# Add-OnV12.net
KiCad netlist of a schematic drawn in EAGLE
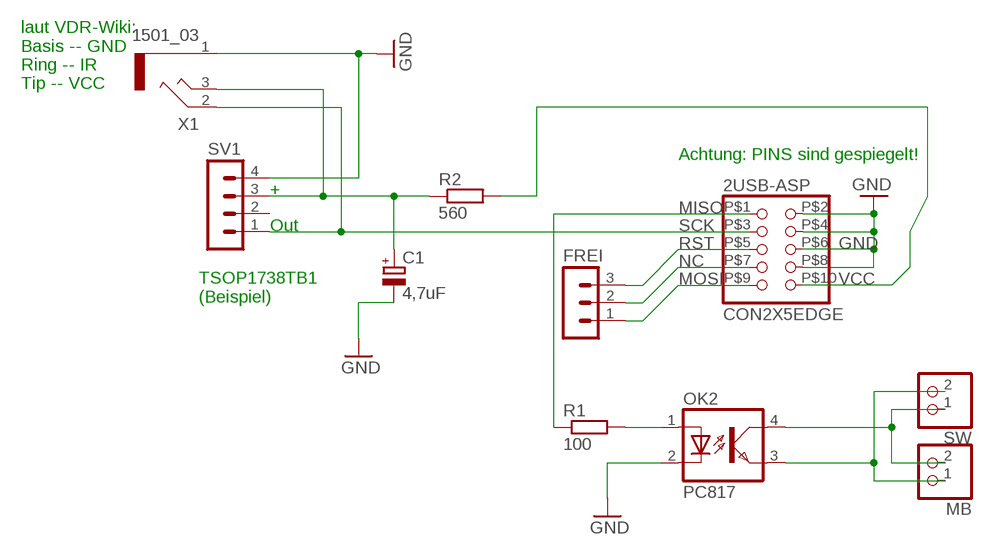
[diagram p0: schematic, sheet 1]

(export (version "E")
  (design (tool "Eeschema 10.0.6"))
  (components
    (comp (ref "2USB-ASP")
      (value "CON2X5EDGE")
      (footprint "eagle-import:CON2X5EDGE")
      (libsource (lib "eagle-import") (part "CON2X5EDGE"))
    )
    (comp (ref "C1")
      (value "4,7uF")
      (footprint "eagle-import:E1,8-4")
      (libsource (lib "eagle-import") (part "CPOL-EUE1.8-4"))
    )
    (comp (ref "FREI")
      (value "MA03-1")
      (footprint "eagle-import:MA03-1")
      (libsource (lib "eagle-import") (part "MA03-1"))
    )
    (comp (ref "MB")
      (value "PINHD-1X2")
      (footprint "eagle-import:1X02")
      (libsource (lib "eagle-import") (part "PINHD-1X2"))
    )
    (comp (ref "OK2")
      (value "PC817")
      (footprint "eagle-import:DIL04")
      (fields (field (name "MPN") "PC817X4J000F"))
      (libsource (lib "eagle-import") (part "PC817"))
    )
    (comp (ref "R1")
      (value "100")
      (footprint "eagle-import:0204V")
      (libsource (lib "eagle-import") (part "R-EU_0204/2V"))
    )
    (comp (ref "R2")
      (value "560")
      (footprint "eagle-import:0204V")
      (libsource (lib "eagle-import") (part "R-EU_0204/2V"))
    )
    (comp (ref "SV1")
      (value "MA04-1")
      (footprint "eagle-import:MA04-1")
      (libsource (lib "eagle-import") (part "MA04-1"))
    )
    (comp (ref "SW")
      (value "PINHD-1X2")
      (footprint "eagle-import:1X02")
      (libsource (lib "eagle-import") (part "PINHD-1X2"))
    )
    (comp (ref "X1")
      (value "1501_03")
      (footprint "eagle-import:1501_03")
      (libsource (lib "eagle-import") (part "1501_03"))
    )
  )
  (nets
    (net (code "1") (name "/MISO") (class "Default")
      (node (ref "2USB-ASP") (pin "P$1") (pinfunction "1_P$1") (pintype "passive"))
      (node (ref "R1") (pin "1") (pinfunction "1_1") (pintype "passive"))
    )
    (net (code "2") (name "/MOSI") (class "Default")
      (node (ref "2USB-ASP") (pin "P$9") (pinfunction "9_P$9") (pintype "passive"))
      (node (ref "FREI") (pin "1") (pinfunction "1_1") (pintype "passive"))
    )
    (net (code "3") (name "/NC") (class "Default")
      (node (ref "2USB-ASP") (pin "P$7") (pinfunction "7_P$7") (pintype "passive"))
      (node (ref "FREI") (pin "2") (pinfunction "2_2") (pintype "passive"))
    )
    (net (code "4") (name "/RST") (class "Default")
      (node (ref "2USB-ASP") (pin "P$5") (pinfunction "5_P$5") (pintype "passive"))
      (node (ref "FREI") (pin "3") (pinfunction "3_3") (pintype "passive"))
    )
    (net (code "5") (name "/SCK") (class "Default")
      (node (ref "2USB-ASP") (pin "P$3") (pinfunction "3_P$3") (pintype "passive"))
      (node (ref "SV1") (pin "1") (pinfunction "1_1") (pintype "passive"))
      (node (ref "X1") (pin "2") (pinfunction "2_2") (pintype "passive"))
    )
    (net (code "6") (name "/VCC") (class "Default")
      (node (ref "2USB-ASP") (pin "P$10") (pinfunction "10_P$10") (pintype "passive"))
      (node (ref "R2") (pin "2") (pinfunction "2_2") (pintype "passive"))
    )
    (net (code "7") (name "GND") (class "Default")
      (node (ref "2USB-ASP") (pin "P$2") (pinfunction "2_P$2") (pintype "passive"))
      (node (ref "2USB-ASP") (pin "P$4") (pinfunction "4_P$4") (pintype "passive"))
      (node (ref "2USB-ASP") (pin "P$6") (pinfunction "6_P$6") (pintype "passive"))
      (node (ref "2USB-ASP") (pin "P$8") (pinfunction "8_P$8") (pintype "passive"))
      (node (ref "C1") (pin "-") (pinfunction "-_-") (pintype "passive"))
      (node (ref "OK2") (pin "2") (pinfunction "C_2") (pintype "passive"))
      (node (ref "SV1") (pin "4") (pinfunction "4_4") (pintype "passive"))
      (node (ref "X1") (pin "1") (pinfunction "1_1") (pintype "passive"))
    )
    (net (code "8") (name "Net-(C1-Pad+)") (class "Default")
      (node (ref "C1") (pin "+") (pinfunction "+_+") (pintype "passive"))
      (node (ref "R2") (pin "1") (pinfunction "1_1") (pintype "passive"))
      (node (ref "SV1") (pin "3") (pinfunction "3_3") (pintype "passive"))
      (node (ref "X1") (pin "3") (pinfunction "3_3") (pintype "passive"))
    )
    (net (code "9") (name "Net-(OK2-A)") (class "Default")
      (node (ref "OK2") (pin "1") (pinfunction "A_1") (pintype "passive"))
      (node (ref "R1") (pin "2") (pinfunction "2_2") (pintype "passive"))
    )
    (net (code "10") (name "Net-(OK2-COL)") (class "Default")
      (node (ref "MB") (pin "2") (pinfunction "2_2") (pintype "passive"))
      (node (ref "OK2") (pin "4") (pinfunction "COL_4") (pintype "passive"))
      (node (ref "SW") (pin "1") (pinfunction "1_1") (pintype "passive"))
    )
    (net (code "11") (name "Net-(OK2-EMIT)") (class "Default")
      (node (ref "MB") (pin "1") (pinfunction "1_1") (pintype "passive"))
      (node (ref "OK2") (pin "3") (pinfunction "EMIT_3") (pintype "passive"))
      (node (ref "SW") (pin "2") (pinfunction "2_2") (pintype "passive"))
    )
    (net (code "12") (name "unconnected-(SV1-Pad2)") (class "Default")
      (node (ref "SV1") (pin "2") (pinfunction "2_2") (pintype "passive"))
    )
  )
)
